# Sheet1.net
KiCad netlist of a schematic drawn in Altium Designer
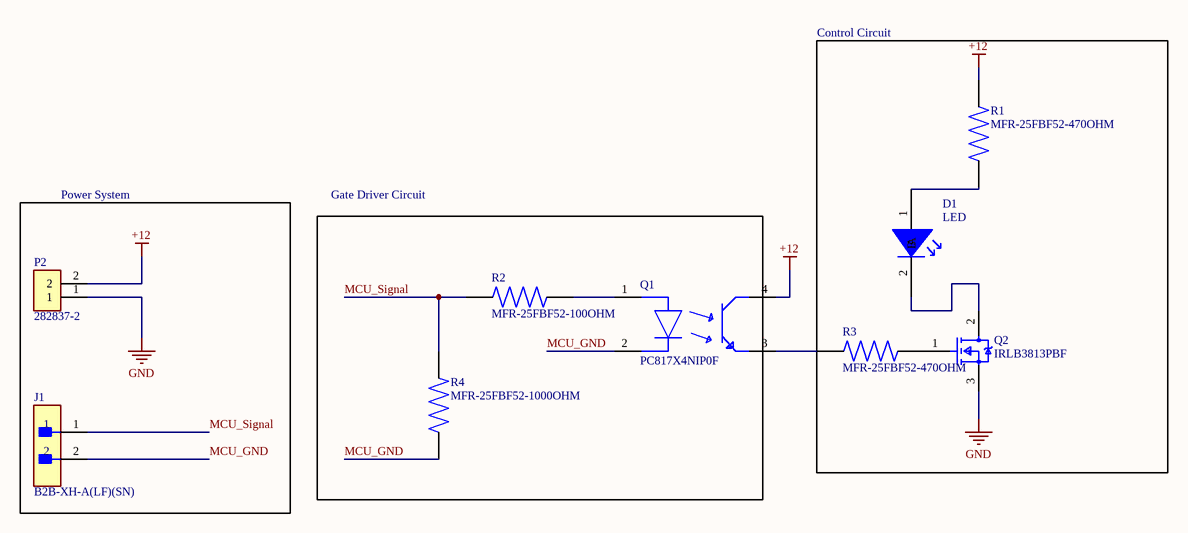
[diagram p0: Sheet1.SchDoc]

(export (version "E")
  (design (tool "Eeschema 10.0.6"))
  (components
    (comp (ref "D1")
      (value "LED")
      (footprint "LED:PCBComponent_1")
      (description "LED RED DIFFUSED T-1 3/4 T/H")
      (fields (field (name "MANUFACTURER") "Kingbright"))
      (libsource (lib "Schlib1") (part "LED"))
    )
    (comp (ref "J1")
      (value "B2B-XH-A(LF)(SN)")
      (footprint "FP-B2B-XH-A_LF_SN-MFG")
      (description "CONN HEADER VERT 2POS 2.5MM")
      (libsource (lib "Altium Content Vault") (part "3bc925449376181038e59eaffc5286c"))
    )
    (comp (ref "P2")
      (value "282837-2")
      (footprint "TE_282837-2")
      (fields (field (name "MF") "TE Connectivity"))
      (libsource (lib "Schlib1") (part "282837-2"))
    )
    (comp (ref "Q1")
      (value "PC817X4NIP0F")
      (footprint "FP-PC817X4NIP0F-MFG")
      (description "Optocoupler DC-IN 1-CH Transistor DC-OUT 4-Pin PDIP SMD")
      (fields (field (name "OCTOPART") "https://octopart.com/pc817x4nip0f-sharp-20650453"))
      (libsource (lib "Altium Content Vault") (part "8ff5844b63c0dea0057760e9ee25456"))
    )
    (comp (ref "Q2")
      (value "IRLB3813PBF")
      (footprint "FP-PG-TO220-3-MFG")
      (description "MOSFET N-CH 30V 260A TO-220AB")
      (fields
        (field (name "OCTOPART") "https://octopart.com/irlb3813pbf-infineon-65874923")
        (field (name "MANUFACTURER") "Infineon")
      )
      (libsource (lib "Schlib1") (part "CMP-32901-000118-1"))
    )
    (comp (ref "R1")
      (value "MFR-25FBF52-470OHM")
      (footprint "RESAD1100W55L680D260")
      (description "1.07 kOhms Â±1% 0.25W, 1/4W Through Hole Resistor Axial - Metal Film")
      (fields (field (name "MF") "Yageo") (field (name "MP") "MFR-25FBF52-1K"))
      (libsource (lib "Schlib1") (part "MFR-25FBF52-1K"))
    )
    (comp (ref "R2")
      (value "MFR-25FBF52-100OHM")
      (footprint "RESAD1100W55L680D260")
      (description "1.07 kOhms Â±1% 0.25W, 1/4W Through Hole Resistor Axial - Metal Film")
      (fields (field (name "MF") "Yageo") (field (name "MP") "MFR-25FBF52-1K"))
      (libsource (lib "Schlib1") (part "MFR-25FBF52-1K"))
    )
    (comp (ref "R3")
      (value "MFR-25FBF52-470OHM")
      (footprint "RESAD1100W55L680D260")
      (description "1.07 kOhms Â±1% 0.25W, 1/4W Through Hole Resistor Axial - Metal Film")
      (fields (field (name "MF") "Yageo") (field (name "MP") "MFR-25FBF52-1K"))
      (libsource (lib "Schlib1") (part "MFR-25FBF52-1K"))
    )
    (comp (ref "R4")
      (value "MFR-25FBF52-1000OHM")
      (footprint "RESAD1100W55L680D260")
      (description "1.07 kOhms Â±1% 0.25W, 1/4W Through Hole Resistor Axial - Metal Film")
      (fields (field (name "MF") "Yageo") (field (name "MP") "MFR-25FBF52-1K"))
      (libsource (lib "Schlib1") (part "MFR-25FBF52-1K"))
    )
  )
  (nets
    (net (code "1") (name "+12") (class "Default")
      (node (ref "P2") (pin "2") (pinfunction "2_2") (pintype "passive"))
      (node (ref "Q1") (pin "4") (pinfunction "C_4") (pintype "passive"))
      (node (ref "R1") (pin "2") (pinfunction "2_2") (pintype "passive"))
    )
    (net (code "2") (name "/MCU_GND") (class "Default")
      (node (ref "J1") (pin "2") (pinfunction "2_2") (pintype "passive"))
      (node (ref "Q1") (pin "2") (pinfunction "C_2") (pintype "passive"))
      (node (ref "R4") (pin "2") (pinfunction "2_2") (pintype "passive"))
    )
    (net (code "3") (name "/MCU_Signal") (class "Default")
      (node (ref "J1") (pin "1") (pinfunction "1_1") (pintype "passive"))
      (node (ref "R2") (pin "2") (pinfunction "2_2") (pintype "passive"))
      (node (ref "R4") (pin "1") (pinfunction "1_1") (pintype "passive"))
    )
    (net (code "4") (name "GND") (class "Default")
      (node (ref "P2") (pin "1") (pinfunction "1_1") (pintype "passive"))
      (node (ref "Q2") (pin "3") (pinfunction "S_3") (pintype "passive"))
    )
    (net (code "5") (name "Net-(D1-A)") (class "Default")
      (node (ref "D1") (pin "1") (pinfunction "A_1") (pintype "passive"))
      (node (ref "R1") (pin "1") (pinfunction "1_1") (pintype "passive"))
    )
    (net (code "6") (name "Net-(D1-B)") (class "Default")
      (node (ref "D1") (pin "2") (pinfunction "B_2") (pintype "passive"))
      (node (ref "Q2") (pin "2") (pinfunction "D_2") (pintype "passive"))
    )
    (net (code "7") (name "Net-(Q1-A)") (class "Default")
      (node (ref "Q1") (pin "1") (pinfunction "A_1") (pintype "passive"))
      (node (ref "R2") (pin "1") (pinfunction "1_1") (pintype "passive"))
    )
    (net (code "8") (name "Net-(Q1-E)") (class "Default")
      (node (ref "Q1") (pin "3") (pinfunction "E_3") (pintype "passive"))
      (node (ref "R3") (pin "2") (pinfunction "2_2") (pintype "passive"))
    )
    (net (code "9") (name "Net-(Q2-G)") (class "Default")
      (node (ref "Q2") (pin "1") (pinfunction "G_1") (pintype "passive"))
      (node (ref "R3") (pin "1") (pinfunction "1_1") (pintype "passive"))
    )
  )
)
